# AC-DC_5V_regulator.net
KiCad netlist of a schematic drawn in EAGLE
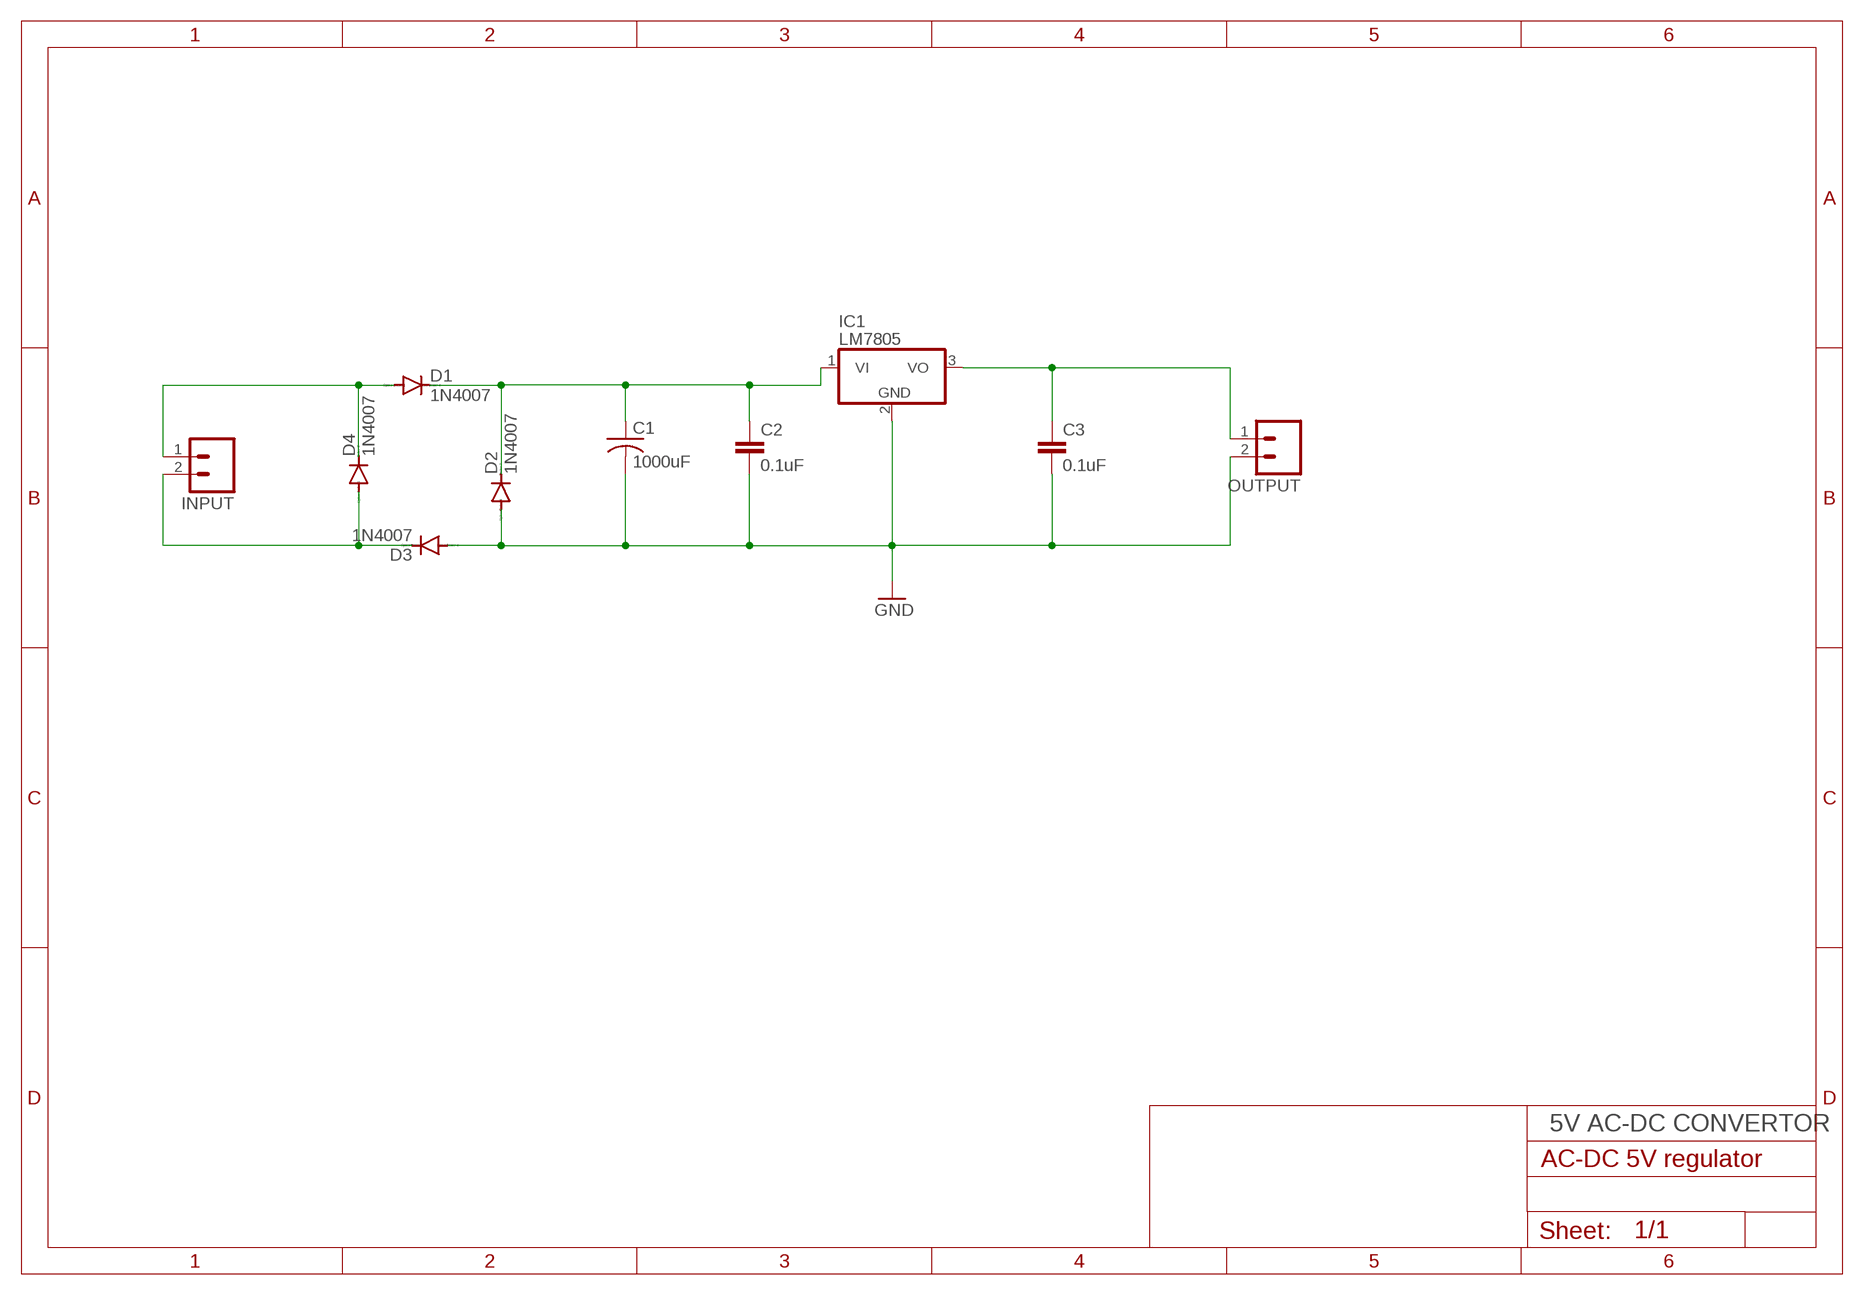
[diagram p0: schematic, sheet 1]

(export (version "E")
  (design (tool "Eeschema 10.0.6"))
  (components
    (comp (ref "C1")
      (value "1000uF")
      (footprint "eagle-import:C025-024X044")
      (libsource (lib "eagle-import") (part "C-US025-024X044"))
    )
    (comp (ref "C2")
      (value "0.1uF")
      (footprint "eagle-import:C025-025X050")
      (libsource (lib "eagle-import") (part "C-EU025-025X050"))
    )
    (comp (ref "C3")
      (value "0.1uF")
      (footprint "eagle-import:C025-025X050")
      (libsource (lib "eagle-import") (part "C-EU025-025X050"))
    )
    (comp (ref "D1")
      (value "1N4007")
      (footprint "eagle-import:DO41-10")
      (libsource (lib "eagle-import") (part "1N4004"))
    )
    (comp (ref "D2")
      (value "1N4007")
      (footprint "eagle-import:DO41-10")
      (libsource (lib "eagle-import") (part "1N4004"))
    )
    (comp (ref "D3")
      (value "1N4007")
      (footprint "eagle-import:DO41-10")
      (libsource (lib "eagle-import") (part "1N4004"))
    )
    (comp (ref "D4")
      (value "1N4007")
      (footprint "eagle-import:DO41-10")
      (libsource (lib "eagle-import") (part "1N4004"))
    )
    (comp (ref "IC1")
      (value "LM7805")
      (footprint "eagle-import:TO220V")
      (libsource (lib "eagle-import") (part "78TV05"))
    )
    (comp (ref "INPUT")
      (value "M02")
      (footprint "eagle-import:02P")
      (libsource (lib "eagle-import") (part "M02"))
    )
    (comp (ref "OUTPUT")
      (value "M02")
      (footprint "eagle-import:02P")
      (libsource (lib "eagle-import") (part "M02"))
    )
  )
  (nets
    (net (code "1") (name "GND") (class "Default")
      (node (ref "C1") (pin "2") (pinfunction "2_2") (pintype "passive"))
      (node (ref "C2") (pin "2") (pinfunction "2_2") (pintype "passive"))
      (node (ref "C3") (pin "2") (pinfunction "2_2") (pintype "passive"))
      (node (ref "D2") (pin "A") (pinfunction "A_A") (pintype "passive"))
      (node (ref "D3") (pin "A") (pinfunction "A_A") (pintype "passive"))
      (node (ref "IC1") (pin "2") (pinfunction "GND_2") (pintype "passive"))
      (node (ref "OUTPUT") (pin "2") (pinfunction "2_2") (pintype "passive"))
    )
    (net (code "2") (name "Net-(D1-PadA)") (class "Default")
      (node (ref "D1") (pin "A") (pinfunction "A_A") (pintype "passive"))
      (node (ref "D4") (pin "C") (pinfunction "C_C") (pintype "passive"))
      (node (ref "INPUT") (pin "1") (pinfunction "1_1") (pintype "passive"))
    )
    (net (code "3") (name "Net-(D3-PadC)") (class "Default")
      (node (ref "D3") (pin "C") (pinfunction "C_C") (pintype "passive"))
      (node (ref "D4") (pin "A") (pinfunction "A_A") (pintype "passive"))
      (node (ref "INPUT") (pin "2") (pinfunction "2_2") (pintype "passive"))
    )
    (net (code "4") (name "Net-(IC1-VI)") (class "Default")
      (node (ref "C1") (pin "1") (pinfunction "1_1") (pintype "passive"))
      (node (ref "C2") (pin "1") (pinfunction "1_1") (pintype "passive"))
      (node (ref "D1") (pin "C") (pinfunction "C_C") (pintype "passive"))
      (node (ref "D2") (pin "C") (pinfunction "C_C") (pintype "passive"))
      (node (ref "IC1") (pin "1") (pinfunction "VI_1") (pintype "input"))
    )
    (net (code "5") (name "Net-(IC1-VO)") (class "Default")
      (node (ref "C3") (pin "1") (pinfunction "1_1") (pintype "passive"))
      (node (ref "IC1") (pin "3") (pinfunction "VO_3") (pintype "passive"))
      (node (ref "OUTPUT") (pin "1") (pinfunction "1_1") (pintype "passive"))
    )
  )
)
